# uc4h_vl53lxx_v0100.net
KiCad netlist of a schematic drawn in EAGLE
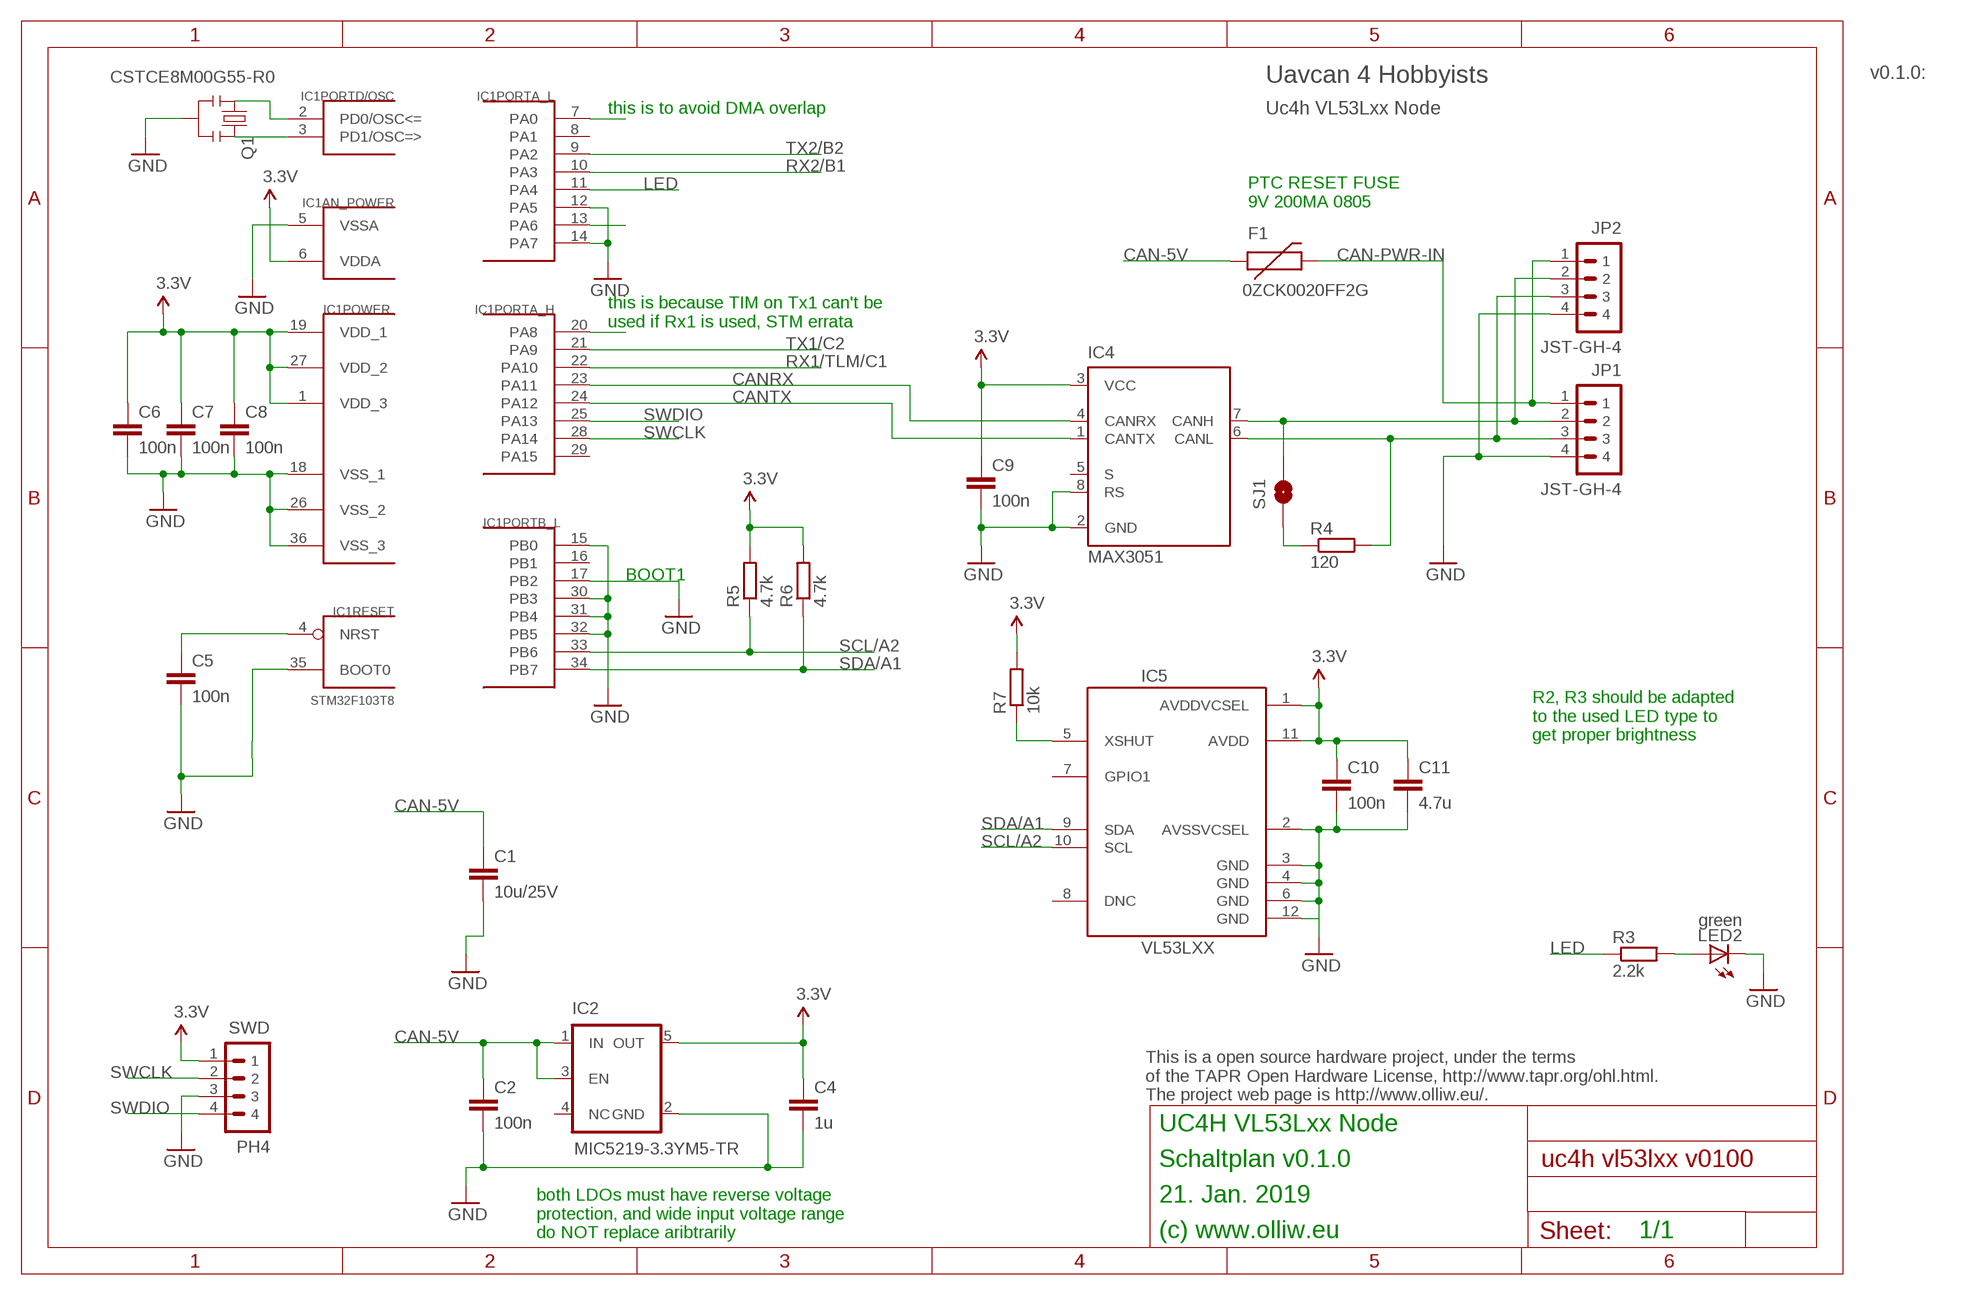
[diagram p0: schematic, sheet 1]

(export (version "E")
  (design (tool "Eeschema 10.0.6"))
  (components
    (comp (ref "C1")
      (value "10u/25V")
      (footprint "eagle-import:C1206")
      (libsource (lib "eagle-import") (part "C-EUC1206"))
    )
    (comp (ref "C2")
      (value "100n")
      (footprint "eagle-import:C0603K")
      (libsource (lib "eagle-import") (part "C-EUC0603K"))
    )
    (comp (ref "C4")
      (value "1u")
      (footprint "eagle-import:C0603K")
      (libsource (lib "eagle-import") (part "C-EUC0603K"))
    )
    (comp (ref "C5")
      (value "100n")
      (footprint "eagle-import:C0402")
      (libsource (lib "eagle-import") (part "C-EUC0402"))
    )
    (comp (ref "C6")
      (value "100n")
      (footprint "eagle-import:C0402")
      (libsource (lib "eagle-import") (part "C-EUC0402"))
    )
    (comp (ref "C7")
      (value "100n")
      (footprint "eagle-import:C0402")
      (libsource (lib "eagle-import") (part "C-EUC0402"))
    )
    (comp (ref "C8")
      (value "100n")
      (footprint "eagle-import:C0402")
      (libsource (lib "eagle-import") (part "C-EUC0402"))
    )
    (comp (ref "C9")
      (value "100n")
      (footprint "eagle-import:C0402")
      (libsource (lib "eagle-import") (part "C-EUC0402"))
    )
    (comp (ref "C10")
      (value "100n")
      (footprint "eagle-import:C0402")
      (libsource (lib "eagle-import") (part "C-EUC0402"))
    )
    (comp (ref "C11")
      (value "4.7u")
      (footprint "eagle-import:C0603K")
      (libsource (lib "eagle-import") (part "C-EUC0603K"))
    )
    (comp (ref "F1")
      (value "0ZCK0020FF2G")
      (footprint "eagle-import:FUSE-0805")
      (libsource (lib "eagle-import") (part "FUSE-PTCFUSE-0805"))
    )
    (comp (ref "IC1")
      (value "STM32F103T8")
      (footprint "eagle-import:VFQFPN36")
      (libsource (lib "eagle-import") (part "STM32F10XTXU6"))
    )
    (comp (ref "IC2")
      (value "MIC5219-3.3YM5-TR")
      (footprint "eagle-import:SOT23-5")
      (libsource (lib "eagle-import") (part "V_REG_TPS76433SOT23-5"))
    )
    (comp (ref "IC4")
      (value "MAX3051")
      (footprint "eagle-import:SOT23-8")
      (libsource (lib "eagle-import") (part "MAX3051"))
    )
    (comp (ref "IC5")
      (value "VL53LXX")
      (footprint "eagle-import:VL53LXX")
      (libsource (lib "eagle-import") (part "VL53LXX"))
    )
    (comp (ref "JP1")
      (value "JST-GH-4")
      (footprint "eagle-import:SM04B-GHS-TB")
      (libsource (lib "eagle-import") (part "JST-GH-4"))
    )
    (comp (ref "JP2")
      (value "JST-GH-4")
      (footprint "eagle-import:SM04B-GHS-TB")
      (libsource (lib "eagle-import") (part "JST-GH-4"))
    )
    (comp (ref "LED2")
      (value "green")
      (footprint "eagle-import:CHIPLED_0603")
      (libsource (lib "eagle-import") (part "LEDCHIPLED_0603"))
    )
    (comp (ref "Q1")
      (value "CSTCE8M00G55-R0")
      (footprint "eagle-import:RESONATOR-SMD")
      (libsource (lib "eagle-import") (part "RESONATORSMD"))
    )
    (comp (ref "R3")
      (value "2.2k")
      (footprint "eagle-import:R0402")
      (libsource (lib "eagle-import") (part "R-EU_R0402"))
    )
    (comp (ref "R4")
      (value "120")
      (footprint "eagle-import:R0402")
      (libsource (lib "eagle-import") (part "R-EU_R0402"))
    )
    (comp (ref "R5")
      (value "4.7k")
      (footprint "eagle-import:R0402")
      (libsource (lib "eagle-import") (part "R-EU_R0402"))
    )
    (comp (ref "R6")
      (value "4.7k")
      (footprint "eagle-import:R0402")
      (libsource (lib "eagle-import") (part "R-EU_R0402"))
    )
    (comp (ref "R7")
      (value "10k")
      (footprint "eagle-import:R0402")
      (libsource (lib "eagle-import") (part "R-EU_R0402"))
    )
    (comp (ref "SJ1")
      (value "SOLDERJUMPERNO")
      (footprint "eagle-import:SJ_2S-NO")
      (libsource (lib "eagle-import") (part "SOLDERJUMPERNO"))
    )
    (comp (ref "SWD")
      (value "PH4")
      (footprint "eagle-import:4X1_1P27_OCT_BILEX")
      (libsource (lib "eagle-import") (part "P4X1_1P27-OCT_BILEX"))
    )
  )
  (nets
    (net (code "1") (name "/CAN-5V") (class "Default")
      (node (ref "C1") (pin "1") (pinfunction "1_1") (pintype "passive"))
      (node (ref "C2") (pin "1") (pinfunction "1_1") (pintype "passive"))
      (node (ref "F1") (pin "1") (pinfunction "1_1") (pintype "bidirectional"))
      (node (ref "IC2") (pin "1") (pinfunction "IN_1") (pintype "power_in"))
      (node (ref "IC2") (pin "3") (pinfunction "EN_3") (pintype "input"))
    )
    (net (code "2") (name "/CAN-PWR-IN") (class "Default")
      (node (ref "F1") (pin "2") (pinfunction "2_2") (pintype "bidirectional"))
      (node (ref "JP1") (pin "1") (pinfunction "1_1") (pintype "passive"))
      (node (ref "JP2") (pin "1") (pinfunction "1_1") (pintype "passive"))
    )
    (net (code "3") (name "/CANRX") (class "Default")
      (node (ref "IC1") (pin "23") (pinfunction "PA11_23") (pintype "bidirectional"))
      (node (ref "IC4") (pin "4") (pinfunction "CANRX_4") (pintype "output"))
    )
    (net (code "4") (name "/CANTX") (class "Default")
      (node (ref "IC1") (pin "24") (pinfunction "PA12_24") (pintype "bidirectional"))
      (node (ref "IC4") (pin "1") (pinfunction "CANTX_1") (pintype "input"))
    )
    (net (code "5") (name "/LED") (class "Default")
      (node (ref "IC1") (pin "11") (pinfunction "PA4_11") (pintype "bidirectional"))
      (node (ref "R3") (pin "1") (pinfunction "1_1") (pintype "passive"))
    )
    (net (code "6") (name "/RX1{slash}TLM{slash}C1") (class "Default")
      (node (ref "IC1") (pin "22") (pinfunction "PA10_22") (pintype "bidirectional"))
    )
    (net (code "7") (name "/RX2{slash}B1") (class "Default")
      (node (ref "IC1") (pin "10") (pinfunction "PA3_10") (pintype "bidirectional"))
    )
    (net (code "8") (name "/SCL{slash}A2") (class "Default")
      (node (ref "IC1") (pin "33") (pinfunction "PB6_33") (pintype "bidirectional"))
      (node (ref "IC5") (pin "10") (pinfunction "SCL_10") (pintype "bidirectional"))
      (node (ref "R5") (pin "1") (pinfunction "1_1") (pintype "passive"))
    )
    (net (code "9") (name "/SDA{slash}A1") (class "Default")
      (node (ref "IC1") (pin "34") (pinfunction "PB7_34") (pintype "bidirectional"))
      (node (ref "IC5") (pin "9") (pinfunction "SDA_9") (pintype "bidirectional"))
      (node (ref "R6") (pin "1") (pinfunction "1_1") (pintype "passive"))
    )
    (net (code "10") (name "/SWCLK") (class "Default")
      (node (ref "IC1") (pin "28") (pinfunction "PA14_28") (pintype "bidirectional"))
      (node (ref "SWD") (pin "2") (pinfunction "2_2") (pintype "passive"))
    )
    (net (code "11") (name "/SWDIO") (class "Default")
      (node (ref "IC1") (pin "25") (pinfunction "PA13_25") (pintype "bidirectional"))
      (node (ref "SWD") (pin "4") (pinfunction "4_4") (pintype "passive"))
    )
    (net (code "12") (name "/TX1{slash}C2") (class "Default")
      (node (ref "IC1") (pin "21") (pinfunction "PA9_21") (pintype "bidirectional"))
    )
    (net (code "13") (name "/TX2{slash}B2") (class "Default")
      (node (ref "IC1") (pin "9") (pinfunction "PA2_9") (pintype "bidirectional"))
    )
    (net (code "14") (name "3.3V") (class "Default")
      (node (ref "C10") (pin "1") (pinfunction "1_1") (pintype "passive"))
      (node (ref "C11") (pin "1") (pinfunction "1_1") (pintype "passive"))
      (node (ref "C4") (pin "1") (pinfunction "1_1") (pintype "passive"))
      (node (ref "C6") (pin "1") (pinfunction "1_1") (pintype "passive"))
      (node (ref "C7") (pin "1") (pinfunction "1_1") (pintype "passive"))
      (node (ref "C8") (pin "1") (pinfunction "1_1") (pintype "passive"))
      (node (ref "C9") (pin "1") (pinfunction "1_1") (pintype "passive"))
      (node (ref "IC1") (pin "1") (pinfunction "VDD_3_1") (pintype "power_in"))
      (node (ref "IC1") (pin "19") (pinfunction "VDD_1_19") (pintype "power_in"))
      (node (ref "IC1") (pin "27") (pinfunction "VDD_2_27") (pintype "power_in"))
      (node (ref "IC1") (pin "6") (pinfunction "VDDA_6") (pintype "power_in"))
      (node (ref "IC2") (pin "5") (pinfunction "OUT_5") (pintype "output"))
      (node (ref "IC4") (pin "3") (pinfunction "VCC_3") (pintype "power_in"))
      (node (ref "IC5") (pin "1") (pinfunction "AVDDVCSEL_1") (pintype "power_in"))
      (node (ref "IC5") (pin "11") (pinfunction "AVDD_11") (pintype "power_in"))
      (node (ref "R5") (pin "2") (pinfunction "2_2") (pintype "passive"))
      (node (ref "R6") (pin "2") (pinfunction "2_2") (pintype "passive"))
      (node (ref "R7") (pin "2") (pinfunction "2_2") (pintype "passive"))
      (node (ref "SWD") (pin "1") (pinfunction "1_1") (pintype "passive"))
    )
    (net (code "15") (name "GND") (class "Default")
      (node (ref "C1") (pin "2") (pinfunction "2_2") (pintype "passive"))
      (node (ref "C10") (pin "2") (pinfunction "2_2") (pintype "passive"))
      (node (ref "C11") (pin "2") (pinfunction "2_2") (pintype "passive"))
      (node (ref "C2") (pin "2") (pinfunction "2_2") (pintype "passive"))
      (node (ref "C4") (pin "2") (pinfunction "2_2") (pintype "passive"))
      (node (ref "C5") (pin "2") (pinfunction "2_2") (pintype "passive"))
      (node (ref "C6") (pin "2") (pinfunction "2_2") (pintype "passive"))
      (node (ref "C7") (pin "2") (pinfunction "2_2") (pintype "passive"))
      (node (ref "C8") (pin "2") (pinfunction "2_2") (pintype "passive"))
      (node (ref "C9") (pin "2") (pinfunction "2_2") (pintype "passive"))
      (node (ref "IC1") (pin "12") (pinfunction "PA5_12") (pintype "bidirectional"))
      (node (ref "IC1") (pin "14") (pinfunction "PA7_14") (pintype "bidirectional"))
      (node (ref "IC1") (pin "15") (pinfunction "PB0_15") (pintype "bidirectional"))
      (node (ref "IC1") (pin "17") (pinfunction "PB2_17") (pintype "bidirectional"))
      (node (ref "IC1") (pin "18") (pinfunction "VSS_1_18") (pintype "power_in"))
      (node (ref "IC1") (pin "26") (pinfunction "VSS_2_26") (pintype "power_in"))
      (node (ref "IC1") (pin "30") (pinfunction "PB3_30") (pintype "bidirectional"))
      (node (ref "IC1") (pin "31") (pinfunction "PB4_31") (pintype "bidirectional"))
      (node (ref "IC1") (pin "32") (pinfunction "PB5_32") (pintype "bidirectional"))
      (node (ref "IC1") (pin "35") (pinfunction "BOOT0_35") (pintype "input"))
      (node (ref "IC1") (pin "36") (pinfunction "VSS_3_36") (pintype "power_in"))
      (node (ref "IC1") (pin "5") (pinfunction "VSSA_5") (pintype "power_in"))
      (node (ref "IC2") (pin "2") (pinfunction "GND_2") (pintype "power_in"))
      (node (ref "IC4") (pin "2") (pinfunction "GND_2") (pintype "power_in"))
      (node (ref "IC4") (pin "8") (pinfunction "RS_8") (pintype "bidirectional"))
      (node (ref "IC5") (pin "12") (pinfunction "GND_12") (pintype "power_in"))
      (node (ref "IC5") (pin "2") (pinfunction "AVSSVCSEL_2") (pintype "input"))
      (node (ref "IC5") (pin "3") (pinfunction "GND_3") (pintype "power_in"))
      (node (ref "IC5") (pin "4") (pinfunction "GND_4") (pintype "power_in"))
      (node (ref "IC5") (pin "6") (pinfunction "GND_6") (pintype "power_in"))
      (node (ref "JP1") (pin "4") (pinfunction "4_4") (pintype "passive"))
      (node (ref "JP2") (pin "4") (pinfunction "4_4") (pintype "passive"))
      (node (ref "LED2") (pin "C") (pinfunction "C_C") (pintype "passive"))
      (node (ref "Q1") (pin "2") (pinfunction "2_2") (pintype "passive"))
      (node (ref "SWD") (pin "3") (pinfunction "3_3") (pintype "passive"))
    )
    (net (code "16") (name "Net-(IC1E-PD0{slash}OSC<=)") (class "Default")
      (node (ref "IC1") (pin "2") (pinfunction "PD0/OSC<=_2") (pintype "bidirectional"))
      (node (ref "Q1") (pin "1") (pinfunction "1_1") (pintype "passive"))
    )
    (net (code "17") (name "Net-(IC1E-PD1{slash}OSC=>)") (class "Default")
      (node (ref "IC1") (pin "3") (pinfunction "PD1/OSC=>_3") (pintype "bidirectional"))
      (node (ref "Q1") (pin "3") (pinfunction "3_3") (pintype "passive"))
    )
    (net (code "18") (name "Net-(IC1G-NRST)") (class "Default")
      (node (ref "C5") (pin "1") (pinfunction "1_1") (pintype "passive"))
      (node (ref "IC1") (pin "4") (pinfunction "NRST_4") (pintype "input"))
    )
    (net (code "19") (name "Net-(IC4-CANH)") (class "Default")
      (node (ref "IC4") (pin "7") (pinfunction "CANH_7") (pintype "bidirectional"))
      (node (ref "JP1") (pin "2") (pinfunction "2_2") (pintype "passive"))
      (node (ref "JP2") (pin "2") (pinfunction "2_2") (pintype "passive"))
      (node (ref "SJ1") (pin "2") (pinfunction "2_2") (pintype "passive"))
    )
    (net (code "20") (name "Net-(IC4-CANL)") (class "Default")
      (node (ref "IC4") (pin "6") (pinfunction "CANL_6") (pintype "bidirectional"))
      (node (ref "JP1") (pin "3") (pinfunction "3_3") (pintype "passive"))
      (node (ref "JP2") (pin "3") (pinfunction "3_3") (pintype "passive"))
      (node (ref "R4") (pin "2") (pinfunction "2_2") (pintype "passive"))
    )
    (net (code "21") (name "Net-(IC5-XSHUT)") (class "Default")
      (node (ref "IC5") (pin "5") (pinfunction "XSHUT_5") (pintype "input"))
      (node (ref "R7") (pin "1") (pinfunction "1_1") (pintype "passive"))
    )
    (net (code "22") (name "Net-(LED2-PadA)") (class "Default")
      (node (ref "LED2") (pin "A") (pinfunction "A_A") (pintype "passive"))
      (node (ref "R3") (pin "2") (pinfunction "2_2") (pintype "passive"))
    )
    (net (code "23") (name "Net-(R4-Pad1)") (class "Default")
      (node (ref "R4") (pin "1") (pinfunction "1_1") (pintype "passive"))
      (node (ref "SJ1") (pin "1") (pinfunction "1_1") (pintype "passive"))
    )
    (net (code "24") (name "unconnected-(IC1B-PA8-Pad20)") (class "Default")
      (node (ref "IC1") (pin "20") (pinfunction "PA8_20") (pintype "bidirectional"))
    )
    (net (code "25") (name "unconnected-(IC1B-PA15-Pad29)") (class "Default")
      (node (ref "IC1") (pin "29") (pinfunction "PA15_29") (pintype "bidirectional"))
    )
    (net (code "26") (name "unconnected-(IC1C-PA0-Pad7)") (class "Default")
      (node (ref "IC1") (pin "7") (pinfunction "PA0_7") (pintype "bidirectional"))
    )
    (net (code "27") (name "unconnected-(IC1C-PA1-Pad8)") (class "Default")
      (node (ref "IC1") (pin "8") (pinfunction "PA1_8") (pintype "bidirectional"))
    )
    (net (code "28") (name "unconnected-(IC1C-PA6-Pad13)") (class "Default")
      (node (ref "IC1") (pin "13") (pinfunction "PA6_13") (pintype "bidirectional"))
    )
    (net (code "29") (name "unconnected-(IC1D-PB1-Pad16)") (class "Default")
      (node (ref "IC1") (pin "16") (pinfunction "PB1_16") (pintype "bidirectional"))
    )
    (net (code "30") (name "unconnected-(IC2-NC-Pad4)") (class "Default")
      (node (ref "IC2") (pin "4") (pinfunction "NC_4") (pintype "passive"))
    )
    (net (code "31") (name "unconnected-(IC4-S-Pad5)") (class "Default")
      (node (ref "IC4") (pin "5") (pinfunction "S_5") (pintype "input"))
    )
    (net (code "32") (name "unconnected-(IC5-DNC-Pad8)") (class "Default")
      (node (ref "IC5") (pin "8") (pinfunction "DNC_8") (pintype "no_connect"))
    )
    (net (code "33") (name "unconnected-(IC5-GPIO1-Pad7)") (class "Default")
      (node (ref "IC5") (pin "7") (pinfunction "GPIO1_7") (pintype "output"))
    )
  )
)
